# MHI-SPI_v1_0withValues.net
KiCad netlist of a schematic drawn in EAGLE
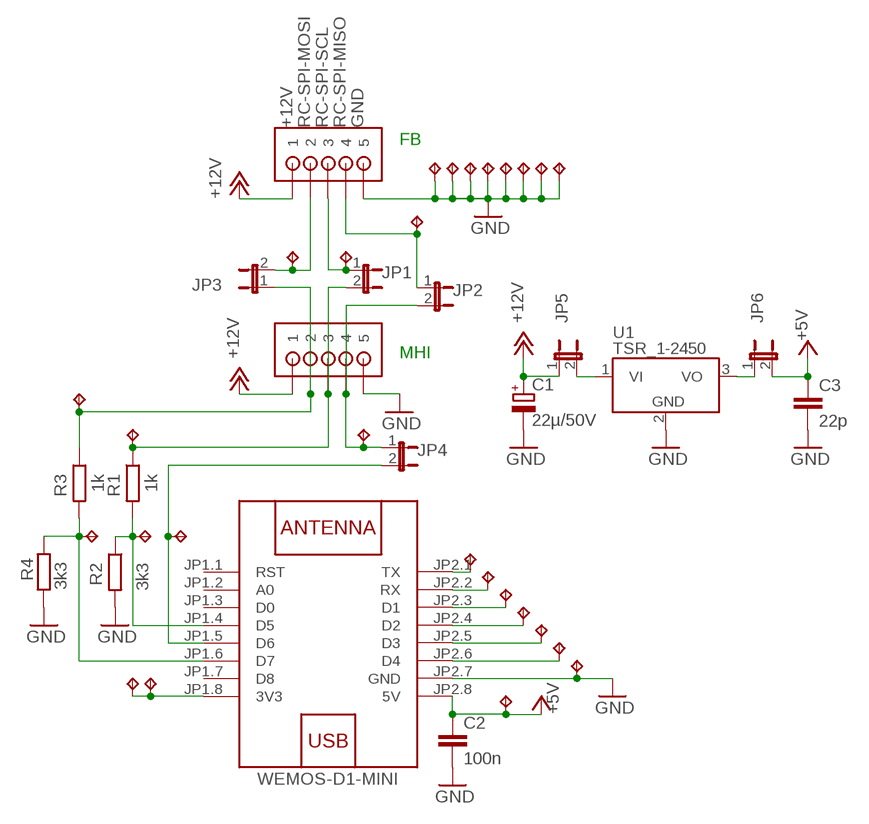
[diagram p0: schematic, sheet 1]

(export (version "E")
  (design (tool "Eeschema 10.0.6"))
  (components
    (comp (ref "C1")
      (value "22µ/50V")
      (footprint "eagle-import:E5-10,5")
      (libsource (lib "eagle-import") (part "CPOL-EUE5-10.5"))
    )
    (comp (ref "C2")
      (value "100n")
      (footprint "eagle-import:C025-024X044")
      (libsource (lib "eagle-import") (part "C-EU025-024X044"))
    )
    (comp (ref "C3")
      (value "22p")
      (footprint "eagle-import:C025-024X044")
      (libsource (lib "eagle-import") (part "C-EU025-024X044"))
    )
    (comp (ref "JP1")
      (value "JP1E")
      (footprint "eagle-import:JP1")
      (libsource (lib "eagle-import") (part "JP1E"))
    )
    (comp (ref "JP2")
      (value "JP1E")
      (footprint "eagle-import:JP1")
      (libsource (lib "eagle-import") (part "JP1E"))
    )
    (comp (ref "JP3")
      (value "JP1E")
      (footprint "eagle-import:JP1")
      (libsource (lib "eagle-import") (part "JP1E"))
    )
    (comp (ref "JP4")
      (value "JP1E")
      (footprint "eagle-import:JP1")
      (libsource (lib "eagle-import") (part "JP1E"))
    )
    (comp (ref "JP5")
      (value "JP1E")
      (footprint "eagle-import:JP1")
      (libsource (lib "eagle-import") (part "JP1E"))
    )
    (comp (ref "JP6")
      (value "JP1E")
      (footprint "eagle-import:JP1")
      (libsource (lib "eagle-import") (part "JP1E"))
    )
    (comp (ref "R1")
      (value "1k")
      (footprint "eagle-import:VMTA55")
      (libsource (lib "eagle-import") (part "R-EU_VMTA55"))
    )
    (comp (ref "R2")
      (value "3k3")
      (footprint "eagle-import:VMTA55")
      (libsource (lib "eagle-import") (part "R-EU_VMTA55"))
    )
    (comp (ref "R3")
      (value "1k")
      (footprint "eagle-import:VMTA55")
      (libsource (lib "eagle-import") (part "R-EU_VMTA55"))
    )
    (comp (ref "R4")
      (value "3k3")
      (footprint "eagle-import:VMTA55")
      (libsource (lib "eagle-import") (part "R-EU_VMTA55"))
    )
    (comp (ref "TP1")
      (value "TPPAD1-13")
      (footprint "eagle-import:P1-13")
      (libsource (lib "eagle-import") (part "TPPAD1-13"))
    )
    (comp (ref "TP2")
      (value "TPPAD1-13")
      (footprint "eagle-import:P1-13")
      (libsource (lib "eagle-import") (part "TPPAD1-13"))
    )
    (comp (ref "TP3")
      (value "TPPAD1-13")
      (footprint "eagle-import:P1-13")
      (libsource (lib "eagle-import") (part "TPPAD1-13"))
    )
    (comp (ref "TP4")
      (value "TPPAD1-13")
      (footprint "eagle-import:P1-13")
      (libsource (lib "eagle-import") (part "TPPAD1-13"))
    )
    (comp (ref "TP5")
      (value "TPPAD1-13")
      (footprint "eagle-import:P1-13")
      (libsource (lib "eagle-import") (part "TPPAD1-13"))
    )
    (comp (ref "TP6")
      (value "TPPAD1-13")
      (footprint "eagle-import:P1-13")
      (libsource (lib "eagle-import") (part "TPPAD1-13"))
    )
    (comp (ref "TP7")
      (value "TPPAD1-13")
      (footprint "eagle-import:P1-13")
      (libsource (lib "eagle-import") (part "TPPAD1-13"))
    )
    (comp (ref "TP8")
      (value "TPPAD1-13")
      (footprint "eagle-import:P1-13")
      (libsource (lib "eagle-import") (part "TPPAD1-13"))
    )
    (comp (ref "TP9")
      (value "TPPAD1-13")
      (footprint "eagle-import:P1-13")
      (libsource (lib "eagle-import") (part "TPPAD1-13"))
    )
    (comp (ref "TP10")
      (value "TPPAD1-13")
      (footprint "eagle-import:P1-13")
      (libsource (lib "eagle-import") (part "TPPAD1-13"))
    )
    (comp (ref "TP11")
      (value "TPPAD1-13")
      (footprint "eagle-import:P1-13")
      (libsource (lib "eagle-import") (part "TPPAD1-13"))
    )
    (comp (ref "TP12")
      (value "TPPAD1-13")
      (footprint "eagle-import:P1-13")
      (libsource (lib "eagle-import") (part "TPPAD1-13"))
    )
    (comp (ref "TP13")
      (value "TPPAD1-13")
      (footprint "eagle-import:P1-13")
      (libsource (lib "eagle-import") (part "TPPAD1-13"))
    )
    (comp (ref "TP14")
      (value "TPPAD1-13")
      (footprint "eagle-import:P1-13")
      (libsource (lib "eagle-import") (part "TPPAD1-13"))
    )
    (comp (ref "TP15")
      (value "TPPAD1-13")
      (footprint "eagle-import:P1-13")
      (libsource (lib "eagle-import") (part "TPPAD1-13"))
    )
    (comp (ref "TP16")
      (value "TPPAD1-13")
      (footprint "eagle-import:P1-13")
      (libsource (lib "eagle-import") (part "TPPAD1-13"))
    )
    (comp (ref "TP17")
      (value "TPPAD1-13")
      (footprint "eagle-import:P1-13")
      (libsource (lib "eagle-import") (part "TPPAD1-13"))
    )
    (comp (ref "TP18")
      (value "TPPAD1-13")
      (footprint "eagle-import:P1-13")
      (libsource (lib "eagle-import") (part "TPPAD1-13"))
    )
    (comp (ref "TP19")
      (value "TPPAD1-13")
      (footprint "eagle-import:P1-13")
      (libsource (lib "eagle-import") (part "TPPAD1-13"))
    )
    (comp (ref "TP20")
      (value "TPPAD1-13")
      (footprint "eagle-import:P1-13")
      (libsource (lib "eagle-import") (part "TPPAD1-13"))
    )
    (comp (ref "TP21")
      (value "TPPAD1-13")
      (footprint "eagle-import:P1-13")
      (libsource (lib "eagle-import") (part "TPPAD1-13"))
    )
    (comp (ref "TP22")
      (value "TPPAD1-13")
      (footprint "eagle-import:P1-13")
      (libsource (lib "eagle-import") (part "TPPAD1-13"))
    )
    (comp (ref "TP23")
      (value "TPPAD1-13")
      (footprint "eagle-import:P1-13")
      (libsource (lib "eagle-import") (part "TPPAD1-13"))
    )
    (comp (ref "TP24")
      (value "TPPAD1-13")
      (footprint "eagle-import:P1-13")
      (libsource (lib "eagle-import") (part "TPPAD1-13"))
    )
    (comp (ref "TP25")
      (value "TPPAD1-13")
      (footprint "eagle-import:P1-13")
      (libsource (lib "eagle-import") (part "TPPAD1-13"))
    )
    (comp (ref "TP26")
      (value "TPPAD1-13")
      (footprint "eagle-import:P1-13")
      (libsource (lib "eagle-import") (part "TPPAD1-13"))
    )
    (comp (ref "TP27")
      (value "TPPAD1-13")
      (footprint "eagle-import:P1-13")
      (libsource (lib "eagle-import") (part "TPPAD1-13"))
    )
    (comp (ref "U$1")
      (value "WEMOS-D1-MINI")
      (footprint "eagle-import:WEMOS-D1-MINI")
      (libsource (lib "eagle-import") (part "WEMOS-D1-MINI"))
    )
    (comp (ref "U$4")
      (value "JST-PH_5-PIN_HEADER")
      (footprint "eagle-import:JST_B5B-PH_HEADER")
      (libsource (lib "eagle-import") (part "JST-PH_5-PIN_HEADER"))
    )
    (comp (ref "U$5")
      (value "JST-PH_5-PIN_HEADER")
      (footprint "eagle-import:JST_B5B-PH_HEADER")
      (libsource (lib "eagle-import") (part "JST-PH_5-PIN_HEADER"))
    )
    (comp (ref "U1")
      (value "TSR_1-2450")
      (footprint "eagle-import:TSR-1")
      (libsource (lib "eagle-import") (part "TSR_1-24_"))
    )
  )
  (nets
    (net (code "1") (name "+5V") (class "Default")
      (node (ref "C2") (pin "1") (pinfunction "1_1") (pintype "passive"))
      (node (ref "C3") (pin "1") (pinfunction "1_1") (pintype "passive"))
      (node (ref "JP6") (pin "2") (pinfunction "2_2") (pintype "passive"))
      (node (ref "TP21") (pin "TP") (pinfunction "TP_TP") (pintype "input"))
      (node (ref "U$1") (pin "JP2.8") (pinfunction "5V_JP2.8") (pintype "power_in"))
    )
    (net (code "2") (name "+12V") (class "Default")
      (node (ref "C1") (pin "+") (pinfunction "+_+") (pintype "passive"))
      (node (ref "JP5") (pin "1") (pinfunction "1_1") (pintype "passive"))
      (node (ref "U$4") (pin "P1") (pinfunction "1_P1") (pintype "bidirectional"))
      (node (ref "U$5") (pin "P1") (pinfunction "1_P1") (pintype "bidirectional"))
    )
    (net (code "3") (name "/RC-SPI-MISO") (class "Default")
      (node (ref "JP2") (pin "1") (pinfunction "1_1") (pintype "passive"))
      (node (ref "TP5") (pin "TP") (pinfunction "TP_TP") (pintype "input"))
      (node (ref "U$4") (pin "P4") (pinfunction "4_P4") (pintype "bidirectional"))
    )
    (net (code "4") (name "/RC-SPI-MOSI") (class "Default")
      (node (ref "JP3") (pin "2") (pinfunction "2_2") (pintype "passive"))
      (node (ref "TP7") (pin "TP") (pinfunction "TP_TP") (pintype "input"))
      (node (ref "U$4") (pin "P2") (pinfunction "2_P2") (pintype "bidirectional"))
    )
    (net (code "5") (name "/RC-SPI-SCL") (class "Default")
      (node (ref "JP1") (pin "1") (pinfunction "1_1") (pintype "passive"))
      (node (ref "TP6") (pin "TP") (pinfunction "TP_TP") (pintype "input"))
      (node (ref "U$4") (pin "P3") (pinfunction "3_P3") (pintype "bidirectional"))
    )
    (net (code "6") (name "GND") (class "Default")
      (node (ref "C1") (pin "-") (pinfunction "-_-") (pintype "passive"))
      (node (ref "C2") (pin "2") (pinfunction "2_2") (pintype "passive"))
      (node (ref "C3") (pin "2") (pinfunction "2_2") (pintype "passive"))
      (node (ref "R2") (pin "2") (pinfunction "2_2") (pintype "passive"))
      (node (ref "R4") (pin "1") (pinfunction "1_1") (pintype "passive"))
      (node (ref "TP1") (pin "TP") (pinfunction "TP_TP") (pintype "input"))
      (node (ref "TP2") (pin "TP") (pinfunction "TP_TP") (pintype "input"))
      (node (ref "TP20") (pin "TP") (pinfunction "TP_TP") (pintype "input"))
      (node (ref "TP24") (pin "TP") (pinfunction "TP_TP") (pintype "input"))
      (node (ref "TP25") (pin "TP") (pinfunction "TP_TP") (pintype "input"))
      (node (ref "TP26") (pin "TP") (pinfunction "TP_TP") (pintype "input"))
      (node (ref "TP27") (pin "TP") (pinfunction "TP_TP") (pintype "input"))
      (node (ref "TP3") (pin "TP") (pinfunction "TP_TP") (pintype "input"))
      (node (ref "TP4") (pin "TP") (pinfunction "TP_TP") (pintype "input"))
      (node (ref "U$1") (pin "JP2.7") (pinfunction "GND_JP2.7") (pintype "power_in"))
      (node (ref "U$4") (pin "P5") (pinfunction "5_P5") (pintype "bidirectional"))
      (node (ref "U$5") (pin "P5") (pinfunction "5_P5") (pintype "bidirectional"))
      (node (ref "U1") (pin "2") (pinfunction "GND_2") (pintype "power_in"))
    )
    (net (code "7") (name "Net-(U$1-3V3)") (class "Default")
      (node (ref "TP22") (pin "TP") (pinfunction "TP_TP") (pintype "input"))
      (node (ref "TP23") (pin "TP") (pinfunction "TP_TP") (pintype "input"))
      (node (ref "U$1") (pin "JP1.8") (pinfunction "3V3_JP1.8") (pintype "power_in"))
    )
    (net (code "8") (name "Net-(U$1-D1)") (class "Default")
      (node (ref "TP16") (pin "TP") (pinfunction "TP_TP") (pintype "input"))
      (node (ref "U$1") (pin "JP2.3") (pinfunction "D1_JP2.3") (pintype "bidirectional"))
    )
    (net (code "9") (name "Net-(U$1-D2)") (class "Default")
      (node (ref "TP17") (pin "TP") (pinfunction "TP_TP") (pintype "input"))
      (node (ref "U$1") (pin "JP2.4") (pinfunction "D2_JP2.4") (pintype "bidirectional"))
    )
    (net (code "10") (name "Net-(U$1-D3)") (class "Default")
      (node (ref "TP18") (pin "TP") (pinfunction "TP_TP") (pintype "input"))
      (node (ref "U$1") (pin "JP2.5") (pinfunction "D3_JP2.5") (pintype "bidirectional"))
    )
    (net (code "11") (name "Net-(U$1-D4)") (class "Default")
      (node (ref "TP19") (pin "TP") (pinfunction "TP_TP") (pintype "input"))
      (node (ref "U$1") (pin "JP2.6") (pinfunction "D4_JP2.6") (pintype "bidirectional"))
    )
    (net (code "12") (name "Net-(U$1-D5)") (class "Default")
      (node (ref "R1") (pin "2") (pinfunction "2_2") (pintype "passive"))
      (node (ref "R2") (pin "1") (pinfunction "1_1") (pintype "passive"))
      (node (ref "TP12") (pin "TP") (pinfunction "TP_TP") (pintype "input"))
      (node (ref "U$1") (pin "JP1.4") (pinfunction "D5_JP1.4") (pintype "bidirectional"))
    )
    (net (code "13") (name "Net-(U$1-D6)") (class "Default")
      (node (ref "JP4") (pin "2") (pinfunction "2_2") (pintype "passive"))
      (node (ref "TP11") (pin "TP") (pinfunction "TP_TP") (pintype "input"))
      (node (ref "U$1") (pin "JP1.5") (pinfunction "D6_JP1.5") (pintype "bidirectional"))
    )
    (net (code "14") (name "Net-(U$1-D7)") (class "Default")
      (node (ref "R3") (pin "2") (pinfunction "2_2") (pintype "passive"))
      (node (ref "R4") (pin "2") (pinfunction "2_2") (pintype "passive"))
      (node (ref "TP13") (pin "TP") (pinfunction "TP_TP") (pintype "input"))
      (node (ref "U$1") (pin "JP1.6") (pinfunction "D7_JP1.6") (pintype "bidirectional"))
    )
    (net (code "15") (name "Net-(U$1-RX)") (class "Default")
      (node (ref "TP15") (pin "TP") (pinfunction "TP_TP") (pintype "input"))
      (node (ref "U$1") (pin "JP2.2") (pinfunction "RX_JP2.2") (pintype "bidirectional"))
    )
    (net (code "16") (name "Net-(U$1-TX)") (class "Default")
      (node (ref "TP14") (pin "TP") (pinfunction "TP_TP") (pintype "input"))
      (node (ref "U$1") (pin "JP2.1") (pinfunction "TX_JP2.1") (pintype "bidirectional"))
    )
    (net (code "17") (name "Net-(U$5-2)") (class "Default")
      (node (ref "JP3") (pin "1") (pinfunction "1_1") (pintype "passive"))
      (node (ref "R3") (pin "1") (pinfunction "1_1") (pintype "passive"))
      (node (ref "TP10") (pin "TP") (pinfunction "TP_TP") (pintype "input"))
      (node (ref "U$5") (pin "P2") (pinfunction "2_P2") (pintype "bidirectional"))
    )
    (net (code "18") (name "Net-(U$5-3)") (class "Default")
      (node (ref "JP1") (pin "2") (pinfunction "2_2") (pintype "passive"))
      (node (ref "R1") (pin "1") (pinfunction "1_1") (pintype "passive"))
      (node (ref "TP9") (pin "TP") (pinfunction "TP_TP") (pintype "input"))
      (node (ref "U$5") (pin "P3") (pinfunction "3_P3") (pintype "bidirectional"))
    )
    (net (code "19") (name "Net-(U$5-4)") (class "Default")
      (node (ref "JP2") (pin "2") (pinfunction "2_2") (pintype "passive"))
      (node (ref "JP4") (pin "1") (pinfunction "1_1") (pintype "passive"))
      (node (ref "TP8") (pin "TP") (pinfunction "TP_TP") (pintype "input"))
      (node (ref "U$5") (pin "P4") (pinfunction "4_P4") (pintype "bidirectional"))
    )
    (net (code "20") (name "Net-(U1-VI)") (class "Default")
      (node (ref "JP5") (pin "2") (pinfunction "2_2") (pintype "passive"))
      (node (ref "U1") (pin "1") (pinfunction "VI_1") (pintype "power_in"))
    )
    (net (code "21") (name "Net-(U1-VO)") (class "Default")
      (node (ref "JP6") (pin "1") (pinfunction "1_1") (pintype "passive"))
      (node (ref "U1") (pin "3") (pinfunction "VO_3") (pintype "power_in"))
    )
    (net (code "22") (name "unconnected-(U$1-A0-PadJP1.2)") (class "Default")
      (node (ref "U$1") (pin "JP1.2") (pinfunction "A0_JP1.2") (pintype "bidirectional"))
    )
    (net (code "23") (name "unconnected-(U$1-D0-PadJP1.3)") (class "Default")
      (node (ref "U$1") (pin "JP1.3") (pinfunction "D0_JP1.3") (pintype "bidirectional"))
    )
    (net (code "24") (name "unconnected-(U$1-D8-PadJP1.7)") (class "Default")
      (node (ref "U$1") (pin "JP1.7") (pinfunction "D8_JP1.7") (pintype "bidirectional"))
    )
    (net (code "25") (name "unconnected-(U$1-RST-PadJP1.1)") (class "Default")
      (node (ref "U$1") (pin "JP1.1") (pinfunction "RST_JP1.1") (pintype "bidirectional"))
    )
  )
)
